# CC2538-CP2102-Zigbee-V01-003.net
KiCad netlist of a schematic drawn in EAGLE
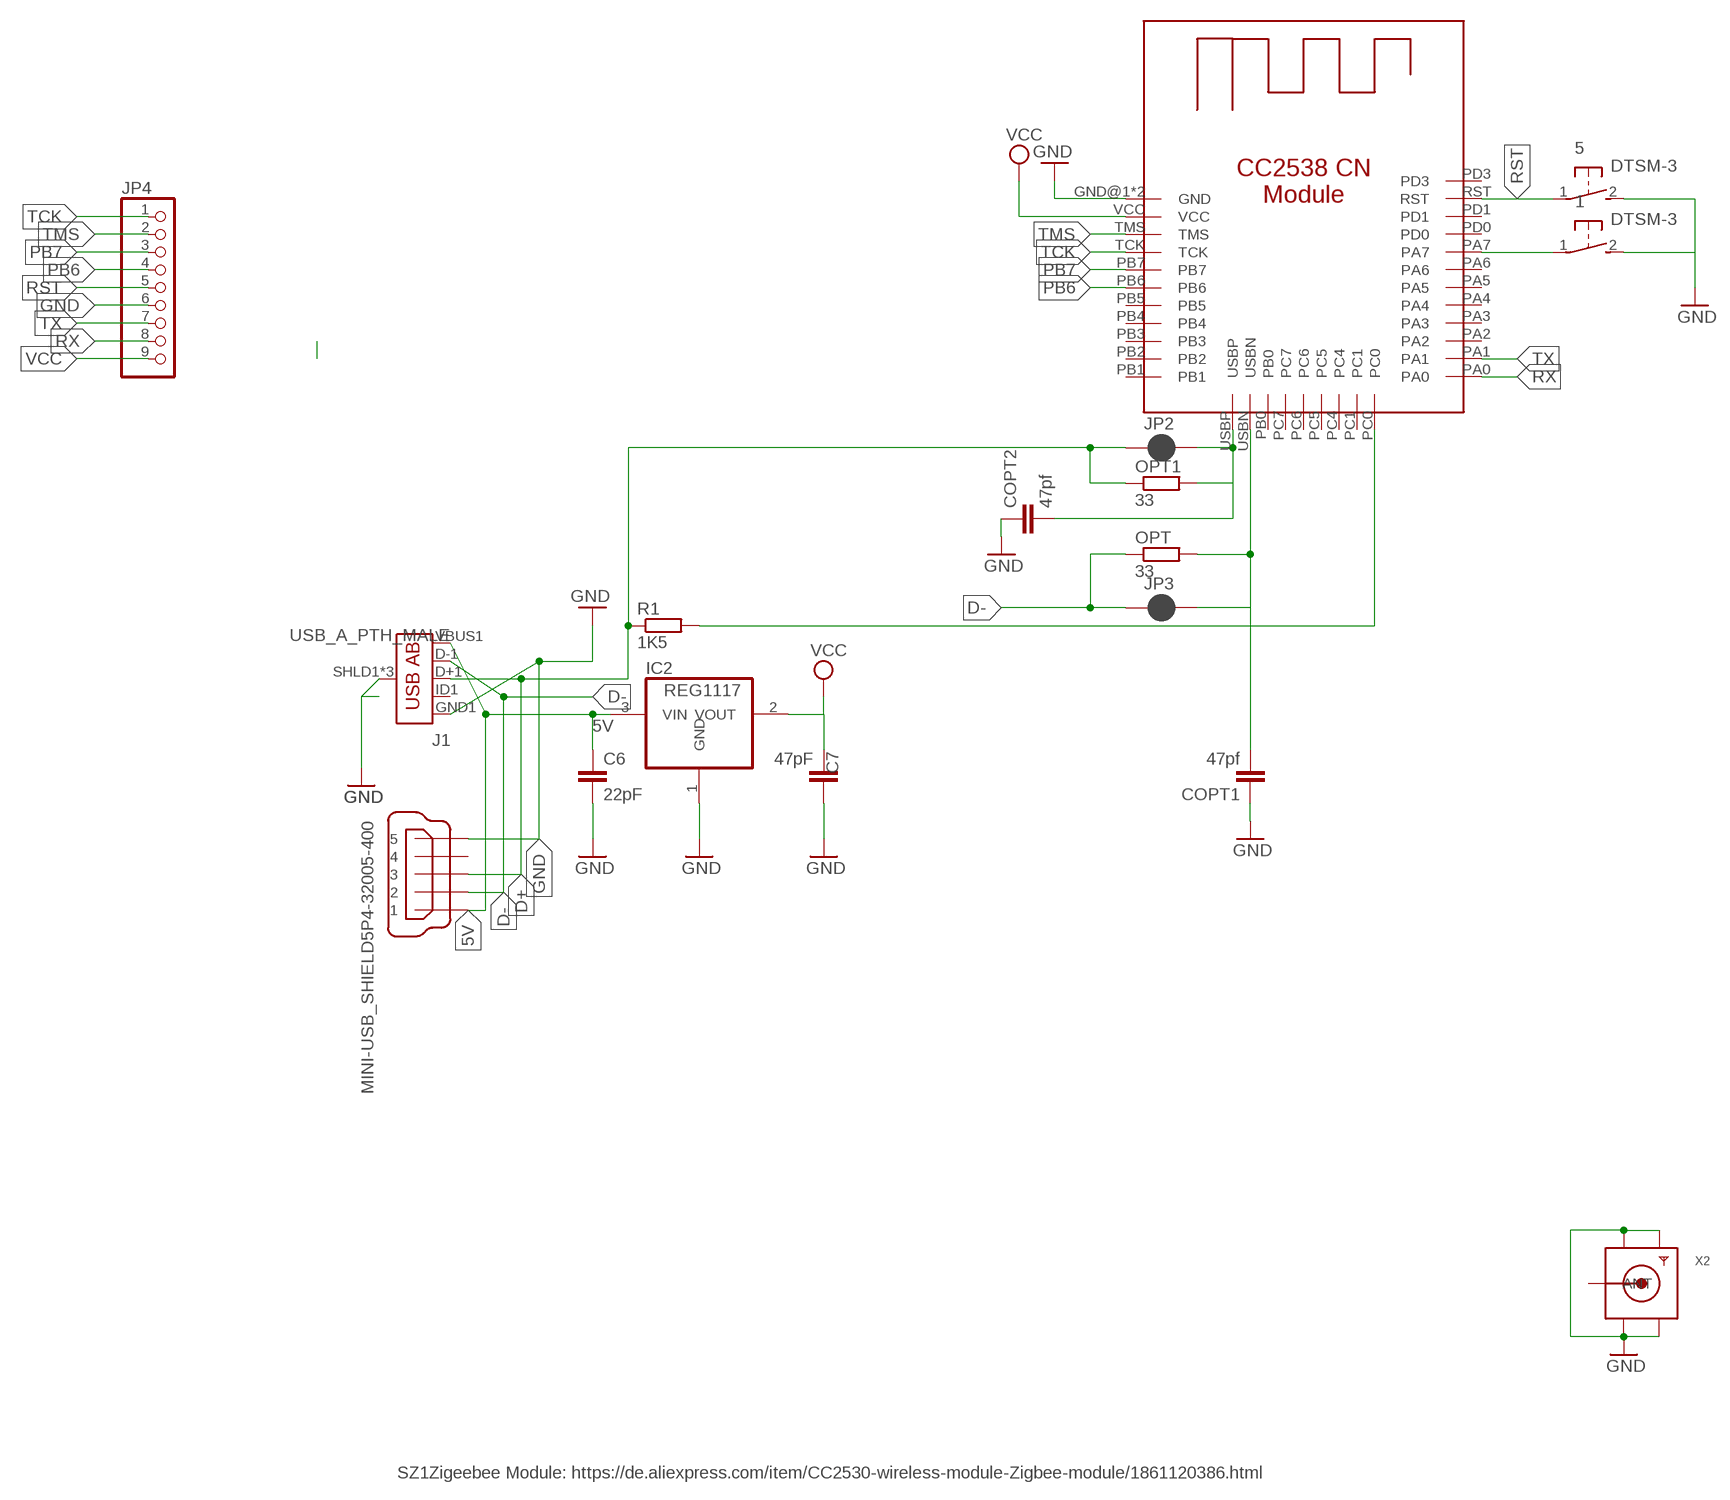
[diagram p0: schematic, sheet 1]

(export (version "E")
  (design (tool "Eeschema 10.0.6"))
  (components
    (comp (ref "1")
      (value "DTSM-3")
      (footprint "eagle-import:DTSM-3")
      (libsource (lib "eagle-import") (part "DTSM-3"))
    )
    (comp (ref "5")
      (value "DTSM-3")
      (footprint "eagle-import:DTSM-3")
      (libsource (lib "eagle-import") (part "DTSM-3"))
    )
    (comp (ref "C6")
      (value "22pF")
      (footprint "eagle-import:C0805")
      (libsource (lib "eagle-import") (part "C-EUC0805"))
    )
    (comp (ref "C7")
      (value "47pF")
      (footprint "eagle-import:C0805")
      (libsource (lib "eagle-import") (part "C-EUC0805"))
    )
    (comp (ref "COPT1")
      (value "47pf")
      (footprint "eagle-import:C0805")
      (libsource (lib "eagle-import") (part "C-EUC0805"))
    )
    (comp (ref "COPT2")
      (value "47pf")
      (footprint "eagle-import:C0805")
      (libsource (lib "eagle-import") (part "C-EUC0805"))
    )
    (comp (ref "IC2")
      (value "REG1117")
      (footprint "eagle-import:SOT223")
      (libsource (lib "eagle-import") (part "REG1117"))
    )
    (comp (ref "J1")
      (value "USB_A_PTH_MALE")
      (footprint "eagle-import:USB-AB-MICRO-SMD")
      (libsource (lib "eagle-import") (part "USB_AB_SMT"))
    )
    (comp (ref "JP2")
      (value "JUMPER-SMT_2_NC_PASTE_NO-SILK")
      (footprint "eagle-import:SMT-JUMPER_2_NC_PASTE_NO-SILK")
      (libsource (lib "eagle-import") (part "JUMPER-SMT_2_NC_PASTE_NO-SILK"))
    )
    (comp (ref "JP3")
      (value "JUMPER-SMT_2_NC_PASTE_NO-SILK")
      (footprint "eagle-import:SMT-JUMPER_2_NC_PASTE_NO-SILK")
      (libsource (lib "eagle-import") (part "JUMPER-SMT_2_NC_PASTE_NO-SILK"))
    )
    (comp (ref "JP4")
      (value "PINHD-1X09_2.54-SMD-90°")
      (footprint "eagle-import:1X09SMD_90")
      (libsource (lib "eagle-import") (part "PINHD-1X09_2.54-SMD-90°"))
    )
    (comp (ref "OPT")
      (value "33")
      (footprint "eagle-import:R0805W")
      (libsource (lib "eagle-import") (part "R-EU_R0805W"))
    )
    (comp (ref "OPT1")
      (value "33")
      (footprint "eagle-import:R0805W")
      (libsource (lib "eagle-import") (part "R-EU_R0805W"))
    )
    (comp (ref "R1")
      (value "1K5")
      (footprint "eagle-import:R0805W")
      (libsource (lib "eagle-import") (part "R-EU_R0805W"))
    )
    (comp (ref "U$3")
      (value "CC2538-CN")
      (footprint "eagle-import:CC2538-CN")
      (libsource (lib "eagle-import") (part "CC2538-CN"))
    )
    (comp (ref "X1")
      (value "MINI-USB_SHIELD5P4-32005-400")
      (footprint "eagle-import:32005-400")
      (libsource (lib "eagle-import") (part "MINI-USB_SHIELD5P4-32005-400"))
    )
    (comp (ref "X2")
      (value "SMACONNECTOR_EDGE")
      (footprint "eagle-import:SMA_EDGELAUNCH")
      (libsource (lib "eagle-import") (part "SMACONNECTOR_EDGE"))
    )
  )
  (nets
    (net (code "1") (name "5V") (class "Default")
      (node (ref "C6") (pin "1") (pinfunction "1_1") (pintype "passive"))
      (node (ref "IC2") (pin "3") (pinfunction "VIN_3") (pintype "input"))
      (node (ref "J1") (pin "VBUS1") (pinfunction "VBUS_VBUS1") (pintype "power_in"))
      (node (ref "X1") (pin "1") (pinfunction "1_1") (pintype "passive"))
    )
    (net (code "2") (name "D+") (class "Default")
      (node (ref "J1") (pin "D+1") (pinfunction "D+_D+1") (pintype "bidirectional"))
      (node (ref "JP2") (pin "1") (pinfunction "1_1") (pintype "passive"))
      (node (ref "OPT1") (pin "1") (pinfunction "1_1") (pintype "passive"))
      (node (ref "R1") (pin "1") (pinfunction "1_1") (pintype "passive"))
      (node (ref "X1") (pin "3") (pinfunction "3_3") (pintype "passive"))
    )
    (net (code "3") (name "D-") (class "Default")
      (node (ref "J1") (pin "D-1") (pinfunction "D-_D-1") (pintype "bidirectional"))
      (node (ref "JP3") (pin "1") (pinfunction "1_1") (pintype "passive"))
      (node (ref "OPT") (pin "1") (pinfunction "1_1") (pintype "passive"))
      (node (ref "X1") (pin "2") (pinfunction "2_2") (pintype "passive"))
    )
    (net (code "4") (name "GND") (class "Default")
      (node (ref "1") (pin "2") (pinfunction "2_2") (pintype "passive"))
      (node (ref "5") (pin "2") (pinfunction "2_2") (pintype "passive"))
      (node (ref "C6") (pin "2") (pinfunction "2_2") (pintype "passive"))
      (node (ref "C7") (pin "1") (pinfunction "1_1") (pintype "passive"))
      (node (ref "COPT1") (pin "1") (pinfunction "1_1") (pintype "passive"))
      (node (ref "COPT2") (pin "1") (pinfunction "1_1") (pintype "passive"))
      (node (ref "IC2") (pin "1") (pinfunction "GND_1") (pintype "power_in"))
      (node (ref "J1") (pin "GND1") (pinfunction "GND_GND1") (pintype "power_in"))
      (node (ref "J1") (pin "SHLD1") (pinfunction "SHIELD_SHLD1") (pintype "bidirectional"))
      (node (ref "J1") (pin "SHLD2") (pinfunction "SHIELD_SHLD2") (pintype "bidirectional"))
      (node (ref "J1") (pin "SHLD3") (pinfunction "SHIELD_SHLD3") (pintype "bidirectional"))
      (node (ref "JP4") (pin "6") (pinfunction "6_6") (pintype "passive"))
      (node (ref "U$3") (pin "GND@1") (pinfunction "GND_GND@1") (pintype "bidirectional"))
      (node (ref "U$3") (pin "GND@2") (pinfunction "GND_GND@2") (pintype "bidirectional"))
      (node (ref "X1") (pin "5") (pinfunction "5_5") (pintype "passive"))
      (node (ref "X2") (pin "GND@1") (pinfunction "GND4_GND@1") (pintype "power_in"))
      (node (ref "X2") (pin "GND@2") (pinfunction "GND3_GND@2") (pintype "power_in"))
      (node (ref "X2") (pin "GND@3") (pinfunction "GND2_GND@3") (pintype "power_in"))
      (node (ref "X2") (pin "GND@4") (pinfunction "GND1_GND@4") (pintype "power_in"))
    )
    (net (code "5") (name "Net-(1-Pad1)") (class "Default")
      (node (ref "1") (pin "1") (pinfunction "1_1") (pintype "passive"))
      (node (ref "U$3") (pin "PA7") (pinfunction "PA7_PA7") (pintype "bidirectional"))
    )
    (net (code "6") (name "Net-(COPT1-Pad2)") (class "Default")
      (node (ref "COPT1") (pin "2") (pinfunction "2_2") (pintype "passive"))
      (node (ref "JP3") (pin "2") (pinfunction "2_2") (pintype "passive"))
      (node (ref "OPT") (pin "2") (pinfunction "2_2") (pintype "passive"))
      (node (ref "U$3") (pin "USBN") (pinfunction "USBN_USBN") (pintype "bidirectional"))
    )
    (net (code "7") (name "Net-(COPT2-Pad2)") (class "Default")
      (node (ref "COPT2") (pin "2") (pinfunction "2_2") (pintype "passive"))
      (node (ref "JP2") (pin "2") (pinfunction "2_2") (pintype "passive"))
      (node (ref "OPT1") (pin "2") (pinfunction "2_2") (pintype "passive"))
      (node (ref "U$3") (pin "USBP") (pinfunction "USBP_USBP") (pintype "bidirectional"))
    )
    (net (code "8") (name "Net-(R1-Pad2)") (class "Default")
      (node (ref "R1") (pin "2") (pinfunction "2_2") (pintype "passive"))
      (node (ref "U$3") (pin "PC0") (pinfunction "PC0_PC0") (pintype "bidirectional"))
    )
    (net (code "9") (name "PB6") (class "Default")
      (node (ref "JP4") (pin "4") (pinfunction "4_4") (pintype "passive"))
      (node (ref "U$3") (pin "PB6") (pinfunction "PB6_PB6") (pintype "bidirectional"))
    )
    (net (code "10") (name "PB7") (class "Default")
      (node (ref "JP4") (pin "3") (pinfunction "3_3") (pintype "passive"))
      (node (ref "U$3") (pin "PB7") (pinfunction "PB7_PB7") (pintype "bidirectional"))
    )
    (net (code "11") (name "RST") (class "Default")
      (node (ref "5") (pin "1") (pinfunction "1_1") (pintype "passive"))
      (node (ref "JP4") (pin "5") (pinfunction "5_5") (pintype "passive"))
      (node (ref "U$3") (pin "RST") (pinfunction "RST_RST") (pintype "bidirectional"))
    )
    (net (code "12") (name "RX") (class "Default")
      (node (ref "JP4") (pin "8") (pinfunction "8_8") (pintype "passive"))
      (node (ref "U$3") (pin "PA0") (pinfunction "PA0_PA0") (pintype "bidirectional"))
    )
    (net (code "13") (name "TCK") (class "Default")
      (node (ref "JP4") (pin "1") (pinfunction "1_1") (pintype "passive"))
      (node (ref "U$3") (pin "TCK") (pinfunction "TCK_TCK") (pintype "bidirectional"))
    )
    (net (code "14") (name "TMS") (class "Default")
      (node (ref "JP4") (pin "2") (pinfunction "2_2") (pintype "passive"))
      (node (ref "U$3") (pin "TMS") (pinfunction "TMS_TMS") (pintype "bidirectional"))
    )
    (net (code "15") (name "TX") (class "Default")
      (node (ref "JP4") (pin "7") (pinfunction "7_7") (pintype "passive"))
      (node (ref "U$3") (pin "PA1") (pinfunction "PA1_PA1") (pintype "bidirectional"))
    )
    (net (code "16") (name "VCC") (class "Default")
      (node (ref "C7") (pin "2") (pinfunction "2_2") (pintype "passive"))
      (node (ref "IC2") (pin "2") (pinfunction "VOUT_2") (pintype "output"))
      (node (ref "JP4") (pin "9") (pinfunction "9_9") (pintype "passive"))
      (node (ref "U$3") (pin "VCC") (pinfunction "VCC_VCC") (pintype "bidirectional"))
    )
    (net (code "17") (name "unconnected-(J1-USBID-PadID1)") (class "Default")
      (node (ref "J1") (pin "ID1") (pinfunction "USBID_ID1") (pintype "bidirectional"))
    )
    (net (code "18") (name "unconnected-(U$3-PadPA2)") (class "Default")
      (node (ref "U$3") (pin "PA2") (pinfunction "PA2_PA2") (pintype "bidirectional"))
    )
    (net (code "19") (name "unconnected-(U$3-PadPA3)") (class "Default")
      (node (ref "U$3") (pin "PA3") (pinfunction "PA3_PA3") (pintype "bidirectional"))
    )
    (net (code "20") (name "unconnected-(U$3-PadPA4)") (class "Default")
      (node (ref "U$3") (pin "PA4") (pinfunction "PA4_PA4") (pintype "bidirectional"))
    )
    (net (code "21") (name "unconnected-(U$3-PadPA5)") (class "Default")
      (node (ref "U$3") (pin "PA5") (pinfunction "PA5_PA5") (pintype "bidirectional"))
    )
    (net (code "22") (name "unconnected-(U$3-PadPA6)") (class "Default")
      (node (ref "U$3") (pin "PA6") (pinfunction "PA6_PA6") (pintype "bidirectional"))
    )
    (net (code "23") (name "unconnected-(U$3-PadPB0)") (class "Default")
      (node (ref "U$3") (pin "PB0") (pinfunction "PB0_PB0") (pintype "bidirectional"))
    )
    (net (code "24") (name "unconnected-(U$3-PadPB1)") (class "Default")
      (node (ref "U$3") (pin "PB1") (pinfunction "PB1_PB1") (pintype "bidirectional"))
    )
    (net (code "25") (name "unconnected-(U$3-PadPB2)") (class "Default")
      (node (ref "U$3") (pin "PB2") (pinfunction "PB2_PB2") (pintype "bidirectional"))
    )
    (net (code "26") (name "unconnected-(U$3-PadPB3)") (class "Default")
      (node (ref "U$3") (pin "PB3") (pinfunction "PB3_PB3") (pintype "bidirectional"))
    )
    (net (code "27") (name "unconnected-(U$3-PadPB4)") (class "Default")
      (node (ref "U$3") (pin "PB4") (pinfunction "PB4_PB4") (pintype "bidirectional"))
    )
    (net (code "28") (name "unconnected-(U$3-PadPB5)") (class "Default")
      (node (ref "U$3") (pin "PB5") (pinfunction "PB5_PB5") (pintype "bidirectional"))
    )
    (net (code "29") (name "unconnected-(U$3-PadPC1)") (class "Default")
      (node (ref "U$3") (pin "PC1") (pinfunction "PC1_PC1") (pintype "bidirectional"))
    )
    (net (code "30") (name "unconnected-(U$3-PadPC4)") (class "Default")
      (node (ref "U$3") (pin "PC4") (pinfunction "PC4_PC4") (pintype "bidirectional"))
    )
    (net (code "31") (name "unconnected-(U$3-PadPC5)") (class "Default")
      (node (ref "U$3") (pin "PC5") (pinfunction "PC5_PC5") (pintype "bidirectional"))
    )
    (net (code "32") (name "unconnected-(U$3-PadPC6)") (class "Default")
      (node (ref "U$3") (pin "PC6") (pinfunction "PC6_PC6") (pintype "bidirectional"))
    )
    (net (code "33") (name "unconnected-(U$3-PadPC7)") (class "Default")
      (node (ref "U$3") (pin "PC7") (pinfunction "PC7_PC7") (pintype "bidirectional"))
    )
    (net (code "34") (name "unconnected-(U$3-PadPD0)") (class "Default")
      (node (ref "U$3") (pin "PD0") (pinfunction "PD0_PD0") (pintype "bidirectional"))
    )
    (net (code "35") (name "unconnected-(U$3-PadPD1)") (class "Default")
      (node (ref "U$3") (pin "PD1") (pinfunction "PD1_PD1") (pintype "bidirectional"))
    )
    (net (code "36") (name "unconnected-(U$3-PadPD3)") (class "Default")
      (node (ref "U$3") (pin "PD3") (pinfunction "PD3_PD3") (pintype "bidirectional"))
    )
    (net (code "37") (name "unconnected-(X1-Pad4)") (class "Default")
      (node (ref "X1") (pin "4") (pinfunction "4_4") (pintype "passive"))
    )
    (net (code "38") (name "unconnected-(X2-ANT-PadP)") (class "Default")
      (node (ref "X2") (pin "P") (pinfunction "ANT_P") (pintype "bidirectional"))
    )
  )
)
